# Sildr_1_1.net
KiCad netlist of a schematic drawn in EAGLE
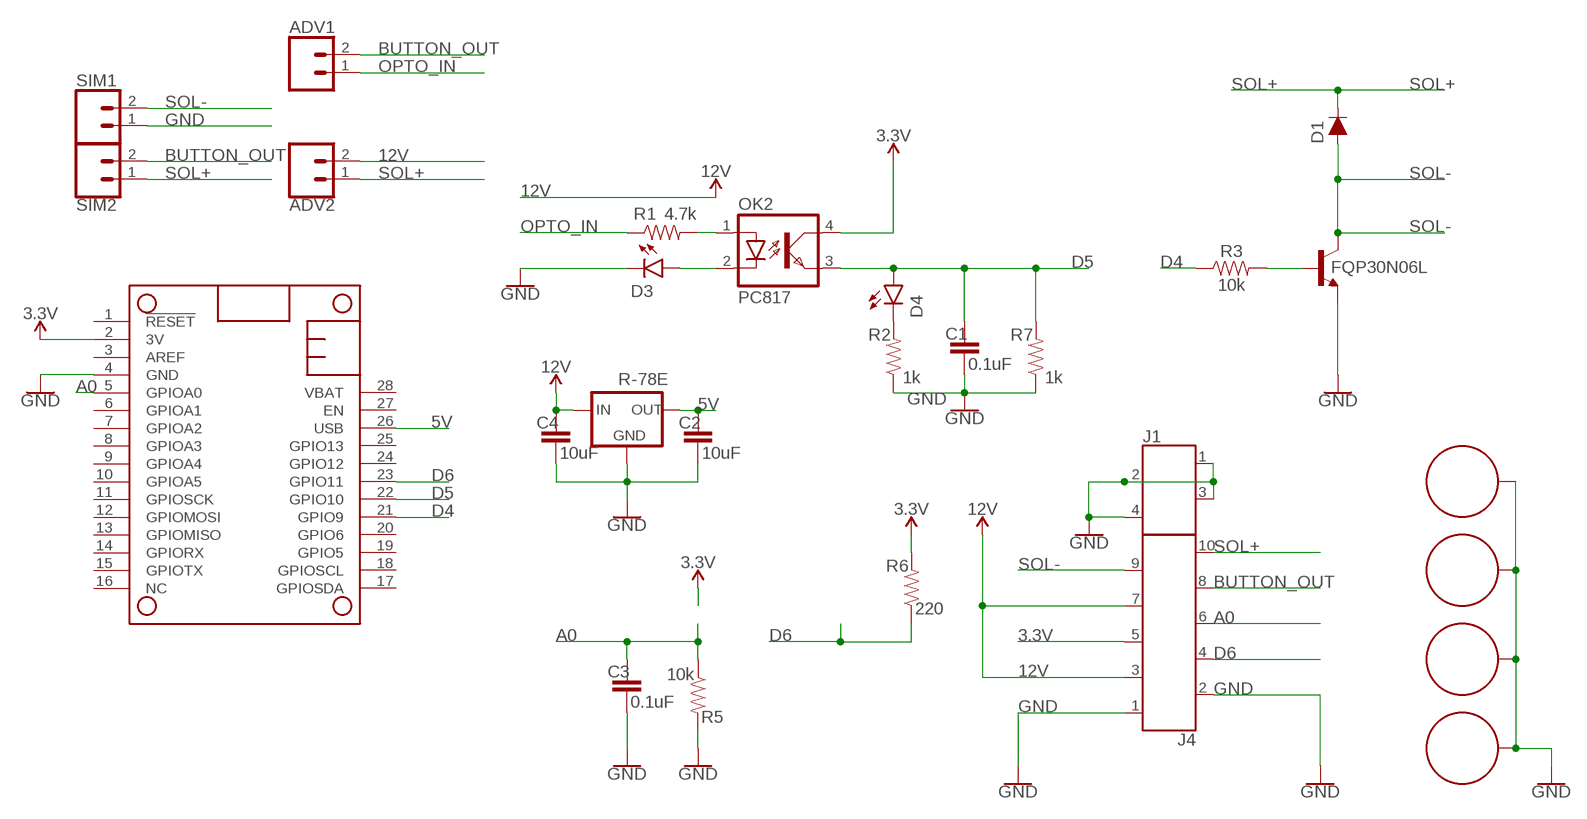
[diagram p0: schematic, sheet 1]

(export (version "E")
  (design (tool "Eeschema 10.0.6"))
  (components
    (comp (ref "ADV1")
      (value "CONN_02")
      (footprint "eagle-import:1X02")
      (libsource (lib "eagle-import") (part "CONN_02"))
    )
    (comp (ref "ADV2")
      (value "CONN_02")
      (footprint "eagle-import:1X02")
      (libsource (lib "eagle-import") (part "CONN_02"))
    )
    (comp (ref "C1")
      (value "0.1uF")
      (footprint "eagle-import:CAP-PTH-SMALL-KIT")
      (libsource (lib "eagle-import") (part "0.1UF-KIT-EZ-50V-20%"))
    )
    (comp (ref "C2")
      (value "10uF")
      (footprint "eagle-import:CAP-PTH-SMALL-KIT")
      (libsource (lib "eagle-import") (part "0.1UF-KIT-EZ-50V-20%"))
    )
    (comp (ref "C3")
      (value "0.1uF")
      (footprint "eagle-import:CAP-PTH-SMALL-KIT")
      (libsource (lib "eagle-import") (part "0.1UF-KIT-EZ-50V-20%"))
    )
    (comp (ref "C4")
      (value "10uF")
      (footprint "eagle-import:CAP-PTH-SMALL-KIT")
      (libsource (lib "eagle-import") (part "0.1UF-KIT-EZ-50V-20%"))
    )
    (comp (ref "D1")
      (value "1A/50V/1.1V")
      (footprint "eagle-import:DIODE-1N4001")
      (libsource (lib "eagle-import") (part "DIODE-PTH"))
    )
    (comp (ref "D3")
      (value "LED3MM")
      (footprint "eagle-import:LED_3MM")
      (libsource (lib "eagle-import") (part "LED3MM"))
    )
    (comp (ref "D4")
      (value "LED3MM")
      (footprint "eagle-import:LED_3MM")
      (libsource (lib "eagle-import") (part "LED3MM"))
    )
    (comp (ref "FQP30N06L")
      (value "2SC1944")
      (footprint "eagle-import:T-30_V")
      (libsource (lib "eagle-import") (part "2SC1944"))
    )
    (comp (ref "H1")
      (value "STANDOFF_ELECTRICAL")
      (footprint "eagle-import:STANDOFF-ELECTRICAL")
      (libsource (lib "eagle-import") (part "STANDOFF_ELECTRICAL"))
    )
    (comp (ref "H2")
      (value "STANDOFF_ELECTRICAL")
      (footprint "eagle-import:STANDOFF-ELECTRICAL")
      (libsource (lib "eagle-import") (part "STANDOFF_ELECTRICAL"))
    )
    (comp (ref "H3")
      (value "STANDOFF_ELECTRICAL")
      (footprint "eagle-import:STANDOFF-ELECTRICAL")
      (libsource (lib "eagle-import") (part "STANDOFF_ELECTRICAL"))
    )
    (comp (ref "H6")
      (value "STANDOFF_ELECTRICAL")
      (footprint "eagle-import:STANDOFF-ELECTRICAL")
      (libsource (lib "eagle-import") (part "STANDOFF_ELECTRICAL"))
    )
    (comp (ref "J1")
      (value "691412320004")
      (footprint "eagle-import:691412320004")
      (libsource (lib "eagle-import") (part "691412320004"))
    )
    (comp (ref "J4")
      (value "691412320010")
      (footprint "eagle-import:691412320010")
      (libsource (lib "eagle-import") (part "691412320010"))
    )
    (comp (ref "MS1")
      (value "FEATHERWING_NODIM")
      (footprint "eagle-import:FEATHERWING_DIM")
      (libsource (lib "eagle-import") (part "FEATHERWING_NODIM"))
    )
    (comp (ref "OK2")
      (value "PC817")
      (footprint "eagle-import:DIL04")
      (fields (field (name "MPN") "PC817X4J000F"))
      (libsource (lib "eagle-import") (part "PC817"))
    )
    (comp (ref "R-78E")
      (value "R-78E5.0-1.0")
      (footprint "eagle-import:DC-DC_CONVERTER_78XX")
      (libsource (lib "eagle-import") (part "R-78E5.0-1.0"))
    )
    (comp (ref "R1")
      (value "4.7k")
      (footprint "eagle-import:AXIAL-0.3")
      (libsource (lib "eagle-import") (part "10KOHM-HORIZ-1/4W-5%"))
    )
    (comp (ref "R2")
      (value "1k")
      (footprint "eagle-import:AXIAL-0.3")
      (libsource (lib "eagle-import") (part "10KOHM-HORIZ-1/4W-5%"))
    )
    (comp (ref "R3")
      (value "10k")
      (footprint "eagle-import:AXIAL-0.3")
      (libsource (lib "eagle-import") (part "10KOHM-HORIZ-1/4W-5%"))
    )
    (comp (ref "R5")
      (value "10k")
      (footprint "eagle-import:AXIAL-0.3")
      (libsource (lib "eagle-import") (part "10KOHM-HORIZ-1/4W-5%"))
    )
    (comp (ref "R6")
      (value "220")
      (footprint "eagle-import:AXIAL-0.3")
      (libsource (lib "eagle-import") (part "10KOHM-HORIZ-1/4W-5%"))
    )
    (comp (ref "R7")
      (value "1k")
      (footprint "eagle-import:AXIAL-0.3")
      (libsource (lib "eagle-import") (part "10KOHM-HORIZ-1/4W-5%"))
    )
    (comp (ref "SIM1")
      (value "CONN_02")
      (footprint "eagle-import:1X02")
      (libsource (lib "eagle-import") (part "CONN_02"))
    )
    (comp (ref "SIM2")
      (value "CONN_02")
      (footprint "eagle-import:1X02")
      (libsource (lib "eagle-import") (part "CONN_02"))
    )
  )
  (nets
    (net (code "1") (name "/5V") (class "Default")
      (node (ref "C2") (pin "1") (pinfunction "1_1") (pintype "passive"))
      (node (ref "MS1") (pin "26") (pinfunction "USB_26") (pintype "power_in"))
      (node (ref "R-78E") (pin "VOUT") (pinfunction "OUT_VOUT") (pintype "passive"))
    )
    (net (code "2") (name "/A0") (class "Default")
      (node (ref "C3") (pin "1") (pinfunction "1_1") (pintype "passive"))
      (node (ref "J4") (pin "6") (pinfunction "6_6") (pintype "passive"))
      (node (ref "MS1") (pin "5") (pinfunction "GPIOA0_5") (pintype "bidirectional"))
      (node (ref "R5") (pin "P$1") (pinfunction "1_P$1") (pintype "passive"))
    )
    (net (code "3") (name "/BUTTON_OUT") (class "Default")
      (node (ref "ADV1") (pin "2") (pinfunction "2_2") (pintype "passive"))
      (node (ref "J4") (pin "8") (pinfunction "8_8") (pintype "passive"))
      (node (ref "SIM2") (pin "2") (pinfunction "2_2") (pintype "passive"))
    )
    (net (code "4") (name "/D4") (class "Default")
      (node (ref "MS1") (pin "21") (pinfunction "GPIO9_21") (pintype "bidirectional"))
      (node (ref "R3") (pin "P$1") (pinfunction "1_P$1") (pintype "passive"))
    )
    (net (code "5") (name "/D5") (class "Default")
      (node (ref "C1") (pin "1") (pinfunction "1_1") (pintype "passive"))
      (node (ref "D4") (pin "A") (pinfunction "A_A") (pintype "passive"))
      (node (ref "MS1") (pin "22") (pinfunction "GPIO10_22") (pintype "bidirectional"))
      (node (ref "OK2") (pin "3") (pinfunction "EMIT_3") (pintype "passive"))
      (node (ref "R7") (pin "P$2") (pinfunction "2_P$2") (pintype "passive"))
    )
    (net (code "6") (name "/D6") (class "Default")
      (node (ref "J4") (pin "4") (pinfunction "4_4") (pintype "passive"))
      (node (ref "MS1") (pin "23") (pinfunction "GPIO11_23") (pintype "bidirectional"))
      (node (ref "R6") (pin "P$1") (pinfunction "1_P$1") (pintype "passive"))
    )
    (net (code "7") (name "/OPTO_IN") (class "Default")
      (node (ref "ADV1") (pin "1") (pinfunction "1_1") (pintype "passive"))
      (node (ref "R1") (pin "P$1") (pinfunction "1_P$1") (pintype "passive"))
    )
    (net (code "8") (name "/SOL+") (class "Default")
      (node (ref "ADV2") (pin "1") (pinfunction "1_1") (pintype "passive"))
      (node (ref "D1") (pin "C") (pinfunction "C_C") (pintype "passive"))
      (node (ref "J4") (pin "10") (pinfunction "10_10") (pintype "passive"))
      (node (ref "SIM2") (pin "1") (pinfunction "1_1") (pintype "passive"))
    )
    (net (code "9") (name "/SOL-") (class "Default")
      (node (ref "D1") (pin "A") (pinfunction "A_A") (pintype "passive"))
      (node (ref "FQP30N06L") (pin "2") (pinfunction "C_2") (pintype "passive"))
      (node (ref "J4") (pin "9") (pinfunction "9_9") (pintype "passive"))
      (node (ref "SIM1") (pin "2") (pinfunction "2_2") (pintype "passive"))
    )
    (net (code "10") (name "/VBAT") (class "Default")
      (node (ref "MS1") (pin "28") (pinfunction "VBAT_28") (pintype "power_in"))
    )
    (net (code "11") (name "3.3V") (class "Default")
      (node (ref "J4") (pin "5") (pinfunction "5_5") (pintype "passive"))
      (node (ref "MS1") (pin "2") (pinfunction "3V_2") (pintype "power_in"))
      (node (ref "OK2") (pin "4") (pinfunction "COL_4") (pintype "passive"))
      (node (ref "R6") (pin "P$2") (pinfunction "2_P$2") (pintype "passive"))
    )
    (net (code "12") (name "12V") (class "Default")
      (node (ref "ADV2") (pin "2") (pinfunction "2_2") (pintype "passive"))
      (node (ref "C4") (pin "1") (pinfunction "1_1") (pintype "passive"))
      (node (ref "J4") (pin "3") (pinfunction "3_3") (pintype "passive"))
      (node (ref "J4") (pin "7") (pinfunction "7_7") (pintype "passive"))
      (node (ref "R-78E") (pin "VIN") (pinfunction "IN_VIN") (pintype "input"))
    )
    (net (code "13") (name "GND") (class "Default")
      (node (ref "C1") (pin "2") (pinfunction "2_2") (pintype "passive"))
      (node (ref "C2") (pin "2") (pinfunction "2_2") (pintype "passive"))
      (node (ref "C3") (pin "2") (pinfunction "2_2") (pintype "passive"))
      (node (ref "C4") (pin "2") (pinfunction "2_2") (pintype "passive"))
      (node (ref "D3") (pin "K") (pinfunction "C_K") (pintype "passive"))
      (node (ref "FQP30N06L") (pin "3") (pinfunction "E_3") (pintype "passive"))
      (node (ref "H1") (pin "P1") (pinfunction "P$1_P1") (pintype "bidirectional"))
      (node (ref "H2") (pin "P1") (pinfunction "P$1_P1") (pintype "bidirectional"))
      (node (ref "H3") (pin "P1") (pinfunction "P$1_P1") (pintype "bidirectional"))
      (node (ref "H6") (pin "P1") (pinfunction "P$1_P1") (pintype "bidirectional"))
      (node (ref "J1") (pin "1") (pinfunction "1_1") (pintype "passive"))
      (node (ref "J1") (pin "2") (pinfunction "2_2") (pintype "passive"))
      (node (ref "J1") (pin "3") (pinfunction "3_3") (pintype "passive"))
      (node (ref "J1") (pin "4") (pinfunction "4_4") (pintype "passive"))
      (node (ref "J4") (pin "1") (pinfunction "1_1") (pintype "passive"))
      (node (ref "J4") (pin "2") (pinfunction "2_2") (pintype "passive"))
      (node (ref "MS1") (pin "4") (pinfunction "GND_4") (pintype "power_in"))
      (node (ref "R-78E") (pin "GND") (pinfunction "GND_GND") (pintype "input"))
      (node (ref "R2") (pin "P$1") (pinfunction "1_P$1") (pintype "passive"))
      (node (ref "R5") (pin "P$2") (pinfunction "2_P$2") (pintype "passive"))
      (node (ref "R7") (pin "P$1") (pinfunction "1_P$1") (pintype "passive"))
      (node (ref "SIM1") (pin "1") (pinfunction "1_1") (pintype "passive"))
    )
    (net (code "14") (name "Net-(D4-C)") (class "Default")
      (node (ref "D4") (pin "K") (pinfunction "C_K") (pintype "passive"))
      (node (ref "R2") (pin "P$2") (pinfunction "2_P$2") (pintype "passive"))
    )
    (net (code "15") (name "Net-(FQP30N06L-B)") (class "Default")
      (node (ref "FQP30N06L") (pin "1") (pinfunction "B_1") (pintype "passive"))
      (node (ref "R3") (pin "P$2") (pinfunction "2_P$2") (pintype "passive"))
    )
    (net (code "16") (name "Net-(OK2-A)") (class "Default")
      (node (ref "OK2") (pin "1") (pinfunction "A_1") (pintype "passive"))
      (node (ref "R1") (pin "P$2") (pinfunction "2_P$2") (pintype "passive"))
    )
    (net (code "17") (name "Net-(OK2-C)") (class "Default")
      (node (ref "D3") (pin "A") (pinfunction "A_A") (pintype "passive"))
      (node (ref "OK2") (pin "2") (pinfunction "C_2") (pintype "passive"))
    )
    (net (code "18") (name "unconnected-(MS1-AREF-Pad3)") (class "Default")
      (node (ref "MS1") (pin "3") (pinfunction "AREF_3") (pintype "passive"))
    )
    (net (code "19") (name "unconnected-(MS1-EN-Pad27)") (class "Default")
      (node (ref "MS1") (pin "27") (pinfunction "EN_27") (pintype "passive"))
    )
    (net (code "20") (name "unconnected-(MS1-GPIO5-Pad19)") (class "Default")
      (node (ref "MS1") (pin "19") (pinfunction "GPIO5_19") (pintype "bidirectional"))
    )
    (net (code "21") (name "unconnected-(MS1-GPIO6-Pad20)") (class "Default")
      (node (ref "MS1") (pin "20") (pinfunction "GPIO6_20") (pintype "bidirectional"))
    )
    (net (code "22") (name "unconnected-(MS1-GPIO12-Pad24)") (class "Default")
      (node (ref "MS1") (pin "24") (pinfunction "GPIO12_24") (pintype "bidirectional"))
    )
    (net (code "23") (name "unconnected-(MS1-GPIO13-Pad25)") (class "Default")
      (node (ref "MS1") (pin "25") (pinfunction "GPIO13_25") (pintype "bidirectional"))
    )
    (net (code "24") (name "unconnected-(MS1-GPIOA1-Pad6)") (class "Default")
      (node (ref "MS1") (pin "6") (pinfunction "GPIOA1_6") (pintype "bidirectional"))
    )
    (net (code "25") (name "unconnected-(MS1-GPIOA2-Pad7)") (class "Default")
      (node (ref "MS1") (pin "7") (pinfunction "GPIOA2_7") (pintype "bidirectional"))
    )
    (net (code "26") (name "unconnected-(MS1-GPIOA3-Pad8)") (class "Default")
      (node (ref "MS1") (pin "8") (pinfunction "GPIOA3_8") (pintype "bidirectional"))
    )
    (net (code "27") (name "unconnected-(MS1-GPIOA4-Pad9)") (class "Default")
      (node (ref "MS1") (pin "9") (pinfunction "GPIOA4_9") (pintype "bidirectional"))
    )
    (net (code "28") (name "unconnected-(MS1-GPIOA5-Pad10)") (class "Default")
      (node (ref "MS1") (pin "10") (pinfunction "GPIOA5_10") (pintype "bidirectional"))
    )
    (net (code "29") (name "unconnected-(MS1-GPIOMISO-Pad13)") (class "Default")
      (node (ref "MS1") (pin "13") (pinfunction "GPIOMISO_13") (pintype "bidirectional"))
    )
    (net (code "30") (name "unconnected-(MS1-GPIOMOSI-Pad12)") (class "Default")
      (node (ref "MS1") (pin "12") (pinfunction "GPIOMOSI_12") (pintype "bidirectional"))
    )
    (net (code "31") (name "unconnected-(MS1-GPIORX-Pad14)") (class "Default")
      (node (ref "MS1") (pin "14") (pinfunction "GPIORX_14") (pintype "bidirectional"))
    )
    (net (code "32") (name "unconnected-(MS1-GPIOSCK-Pad11)") (class "Default")
      (node (ref "MS1") (pin "11") (pinfunction "GPIOSCK_11") (pintype "bidirectional"))
    )
    (net (code "33") (name "unconnected-(MS1-GPIOSCL-Pad18)") (class "Default")
      (node (ref "MS1") (pin "18") (pinfunction "GPIOSCL_18") (pintype "bidirectional"))
    )
    (net (code "34") (name "unconnected-(MS1-GPIOSDA-Pad17)") (class "Default")
      (node (ref "MS1") (pin "17") (pinfunction "GPIOSDA_17") (pintype "bidirectional"))
    )
    (net (code "35") (name "unconnected-(MS1-GPIOTX-Pad15)") (class "Default")
      (node (ref "MS1") (pin "15") (pinfunction "GPIOTX_15") (pintype "bidirectional"))
    )
    (net (code "36") (name "unconnected-(MS1-NC-Pad16)") (class "Default")
      (node (ref "MS1") (pin "16") (pinfunction "NC_16") (pintype "passive"))
    )
    (net (code "37") (name "unconnected-(MS1-~{RESET}-Pad1)") (class "Default")
      (node (ref "MS1") (pin "1") (pinfunction "~{RESET}_1") (pintype "input"))
    )
  )
)
